# LoRaAntenna.net
KiCad netlist of a schematic drawn in Altium Designer
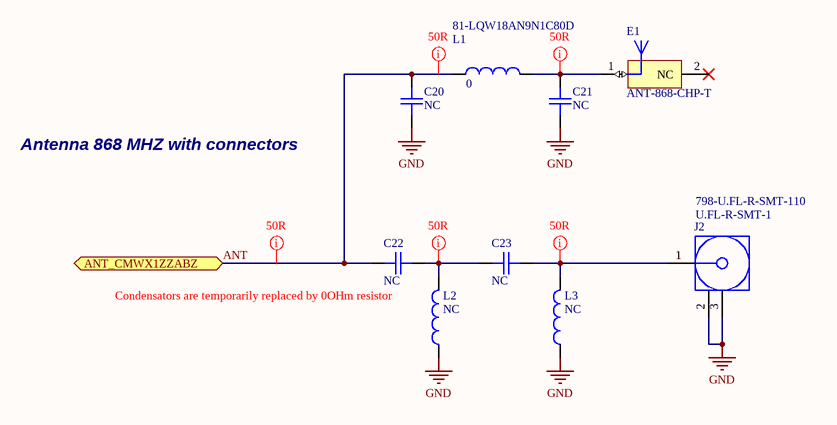
[diagram p0: LoRaAntenna.SchDoc]

(export (version "E")
  (design (tool "Eeschema 10.0.6"))
  (components
    (comp (ref "C20")
      (value "NC")
      (footprint "CAPC1608X08")
      (description "MLCC Capacitor 1608")
      (libsource (lib "HEPIA Vault") (part "CMP-001-0010-A.3"))
    )
    (comp (ref "C21")
      (value "NC")
      (footprint "CAPC1608X08")
      (description "MLCC Capacitor 1608")
      (libsource (lib "HEPIA Vault") (part "CMP-001-0010-A.3"))
    )
    (comp (ref "C22")
      (value "NC")
      (footprint "CAPC1608X08")
      (description "MLCC Capacitor 1608")
      (libsource (lib "HEPIA Vault") (part "CMP-001-0010-A.3"))
    )
    (comp (ref "C23")
      (value "NC")
      (footprint "CAPC1608X08")
      (description "MLCC Capacitor 1608")
      (libsource (lib "HEPIA Vault") (part "CMP-001-0010-A.3"))
    )
    (comp (ref "E1")
      (value "ANT-868-CHP-T")
      (footprint "ANT-868-916-CHP")
      (description "1/4-wave Monopole Ultra-Compact Chip Antenna, CHP Series, 868MHz, Tape and Reel")
      (libsource (lib "HEPIA Vault") (part "ANT-XXX-CHP"))
    )
    (comp (ref "J2")
      (value "U.FL-R-SMT-1")
      (footprint "U.FL-R-SMT-1")
      (description "Hirose U.FL SMT connector")
      (fields (field (name "SUPPLIER PART NUMBER 1") "798-U.FL-R-SMT-110"))
      (libsource (lib "HEPIA Vault") (part "CMP-001-0013-A.3"))
    )
    (comp (ref "L1")
      (value "0")
      (footprint "INDC1608X08")
      (description "Ferrite Beads 1608")
      (fields (field (name "SUPPLIER PART NUMBER 1") "81-LQW18AN9N1C80D"))
      (libsource (lib "HEPIA Vault") (part "CMP-001-0101-A.4"))
    )
    (comp (ref "L2")
      (value "NC")
      (footprint "INDC1608X08")
      (description "Ferrite Beads 1608")
      (libsource (lib "HEPIA Vault") (part "CMP-001-0101-A.4"))
    )
    (comp (ref "L3")
      (value "NC")
      (footprint "INDC1608X08")
      (description "Ferrite Beads 1608")
      (libsource (lib "HEPIA Vault") (part "CMP-001-0101-A.4"))
    )
  )
  (nets
    (net (code "1") (name "/ANT") (class "Default")
      (node (ref "C20") (pin "2") (pinfunction "2_2") (pintype "passive"))
      (node (ref "C22") (pin "1") (pinfunction "1_1") (pintype "passive"))
      (node (ref "L1") (pin "1") (pinfunction "1_1") (pintype "passive"))
    )
    (net (code "2") (name "GND") (class "Default")
      (node (ref "C20") (pin "1") (pinfunction "1_1") (pintype "passive"))
      (node (ref "C21") (pin "1") (pinfunction "1_1") (pintype "passive"))
      (node (ref "J2") (pin "2") (pinfunction "GND_2") (pintype "power_in"))
      (node (ref "J2") (pin "3") (pinfunction "GND_3") (pintype "power_in"))
      (node (ref "L2") (pin "1") (pinfunction "1_1") (pintype "passive"))
      (node (ref "L3") (pin "1") (pinfunction "1_1") (pintype "passive"))
    )
    (net (code "3") (name "Net-(C22-Pad2)") (class "Default")
      (node (ref "C22") (pin "2") (pinfunction "2_2") (pintype "passive"))
      (node (ref "C23") (pin "1") (pinfunction "1_1") (pintype "passive"))
      (node (ref "L2") (pin "2") (pinfunction "2_2") (pintype "passive"))
    )
    (net (code "4") (name "Net-(E1-FEED)") (class "Default")
      (node (ref "C21") (pin "2") (pinfunction "2_2") (pintype "passive"))
      (node (ref "E1") (pin "1") (pinfunction "FEED_1") (pintype "bidirectional"))
      (node (ref "L1") (pin "2") (pinfunction "2_2") (pintype "passive"))
    )
    (net (code "5") (name "Net-(J2-Signal)") (class "Default")
      (node (ref "C23") (pin "2") (pinfunction "2_2") (pintype "passive"))
      (node (ref "J2") (pin "1") (pinfunction "Signal_1") (pintype "passive"))
      (node (ref "L3") (pin "2") (pinfunction "2_2") (pintype "passive"))
    )
    (net (code "6") (name "unconnected-(E1-NC-Pad2)") (class "Default")
      (node (ref "E1") (pin "2") (pinfunction "NC_2") (pintype "passive+no_connect"))
    )
  )
)
